# LE1-4.net
KiCad netlist of a schematic drawn in EAGLE
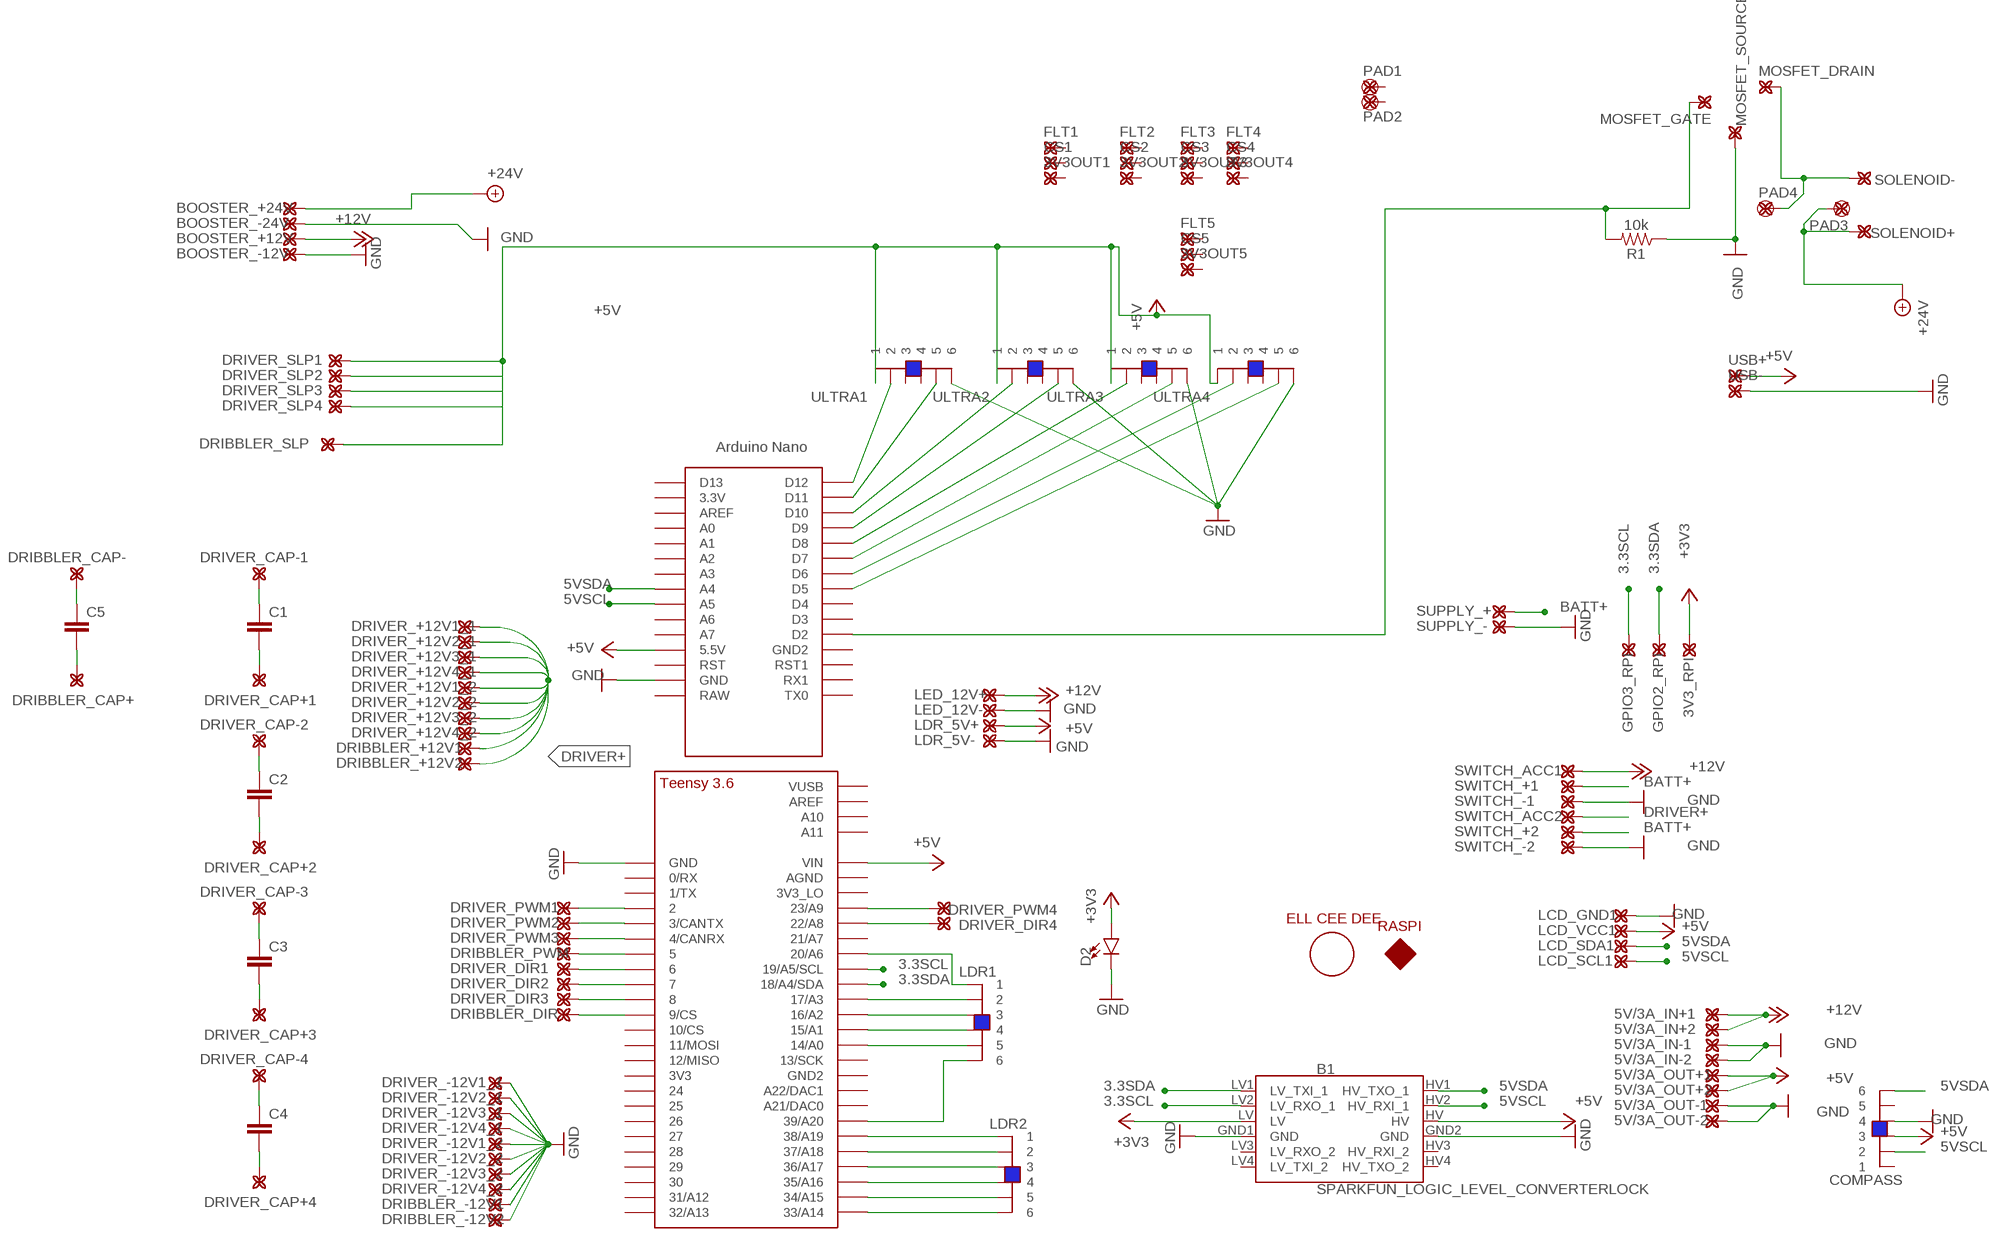
[diagram p0: schematic, sheet 1]

(export (version "E")
  (design (tool "Eeschema 10.0.6"))
  (components
    (comp (ref "3V3OUT1")
      (value "BETTERPAD_2.54")
      (footprint "eagle-import:SUPERIORSIM")
      (libsource (lib "eagle-import") (part "BETTERPAD_2.54"))
    )
    (comp (ref "3V3OUT2")
      (value "BETTERPAD_2.54")
      (footprint "eagle-import:SUPERIORSIM")
      (libsource (lib "eagle-import") (part "BETTERPAD_2.54"))
    )
    (comp (ref "3V3OUT3")
      (value "BETTERPAD_2.54")
      (footprint "eagle-import:SUPERIORSIM")
      (libsource (lib "eagle-import") (part "BETTERPAD_2.54"))
    )
    (comp (ref "3V3OUT4")
      (value "BETTERPAD_2.54")
      (footprint "eagle-import:SUPERIORSIM")
      (libsource (lib "eagle-import") (part "BETTERPAD_2.54"))
    )
    (comp (ref "3V3OUT5")
      (value "BETTERPAD_2.54")
      (footprint "eagle-import:SUPERIORSIM")
      (libsource (lib "eagle-import") (part "BETTERPAD_2.54"))
    )
    (comp (ref "3V3_RPI")
      (value "BETTERPAD_2.54")
      (footprint "eagle-import:SUPERIORSIM")
      (libsource (lib "eagle-import") (part "BETTERPAD_2.54"))
    )
    (comp (ref "5V/3A_IN+1")
      (value "BETTERPAD_2.54")
      (footprint "eagle-import:SUPERIORSIM")
      (libsource (lib "eagle-import") (part "BETTERPAD_2.54"))
    )
    (comp (ref "5V/3A_IN+2")
      (value "BETTERPAD_2.54")
      (footprint "eagle-import:SUPERIORSIM")
      (libsource (lib "eagle-import") (part "BETTERPAD_2.54"))
    )
    (comp (ref "5V/3A_IN-1")
      (value "BETTERPAD_2.54")
      (footprint "eagle-import:SUPERIORSIM")
      (libsource (lib "eagle-import") (part "BETTERPAD_2.54"))
    )
    (comp (ref "5V/3A_IN-2")
      (value "BETTERPAD_2.54")
      (footprint "eagle-import:SUPERIORSIM")
      (libsource (lib "eagle-import") (part "BETTERPAD_2.54"))
    )
    (comp (ref "5V/3A_OUT+1")
      (value "BETTERPAD_2.54")
      (footprint "eagle-import:SUPERIORSIM")
      (libsource (lib "eagle-import") (part "BETTERPAD_2.54"))
    )
    (comp (ref "5V/3A_OUT+2")
      (value "BETTERPAD_2.54")
      (footprint "eagle-import:SUPERIORSIM")
      (libsource (lib "eagle-import") (part "BETTERPAD_2.54"))
    )
    (comp (ref "5V/3A_OUT-1")
      (value "BETTERPAD_2.54")
      (footprint "eagle-import:SUPERIORSIM")
      (libsource (lib "eagle-import") (part "BETTERPAD_2.54"))
    )
    (comp (ref "5V/3A_OUT-2")
      (value "BETTERPAD_2.54")
      (footprint "eagle-import:SUPERIORSIM")
      (libsource (lib "eagle-import") (part "BETTERPAD_2.54"))
    )
    (comp (ref "B1")
      (value "SPARKFUN_LOGIC_LEVEL_CONVERTERLOCK")
      (footprint "eagle-import:SPARKFUN_LOGIC_LEVEL_CONVERTER_LOCK")
      (libsource (lib "eagle-import") (part "SPARKFUN_LOGIC_LEVEL_CONVERTERLOCK"))
    )
    (comp (ref "BOOSTER_+12V")
      (value "BETTERPAD_2.54")
      (footprint "eagle-import:SUPERIORSIM")
      (libsource (lib "eagle-import") (part "BETTERPAD_2.54"))
    )
    (comp (ref "BOOSTER_+24V")
      (value "BETTERPAD_2.54")
      (footprint "eagle-import:SUPERIORSIM")
      (libsource (lib "eagle-import") (part "BETTERPAD_2.54"))
    )
    (comp (ref "BOOSTER_-12V")
      (value "BETTERPAD_2.54")
      (footprint "eagle-import:SUPERIORSIM")
      (libsource (lib "eagle-import") (part "BETTERPAD_2.54"))
    )
    (comp (ref "BOOSTER_-24V")
      (value "BETTERPAD_2.54")
      (footprint "eagle-import:SUPERIORSIM")
      (libsource (lib "eagle-import") (part "BETTERPAD_2.54"))
    )
    (comp (ref "C1")
      (value "C5/7.2")
      (footprint "eagle-import:C5B7.2")
      (libsource (lib "eagle-import") (part "C5/7.2"))
    )
    (comp (ref "C2")
      (value "C5/7.2")
      (footprint "eagle-import:C5B7.2")
      (libsource (lib "eagle-import") (part "C5/7.2"))
    )
    (comp (ref "C3")
      (value "C5/7.2")
      (footprint "eagle-import:C5B7.2")
      (libsource (lib "eagle-import") (part "C5/7.2"))
    )
    (comp (ref "C4")
      (value "C5/7.2")
      (footprint "eagle-import:C5B7.2")
      (libsource (lib "eagle-import") (part "C5/7.2"))
    )
    (comp (ref "C5")
      (value "C5/7.2")
      (footprint "eagle-import:C5B7.2")
      (libsource (lib "eagle-import") (part "C5/7.2"))
    )
    (comp (ref "COMPASS")
      (value "6P6C_FEMALESMD")
      (footprint "eagle-import:6P6C_FEMALE")
      (libsource (lib "eagle-import") (part "6P6C_FEMALESMD"))
    )
    (comp (ref "CS1")
      (value "BETTERPAD_2.54")
      (footprint "eagle-import:SUPERIORSIM")
      (libsource (lib "eagle-import") (part "BETTERPAD_2.54"))
    )
    (comp (ref "CS2")
      (value "BETTERPAD_2.54")
      (footprint "eagle-import:SUPERIORSIM")
      (libsource (lib "eagle-import") (part "BETTERPAD_2.54"))
    )
    (comp (ref "CS3")
      (value "BETTERPAD_2.54")
      (footprint "eagle-import:SUPERIORSIM")
      (libsource (lib "eagle-import") (part "BETTERPAD_2.54"))
    )
    (comp (ref "CS4")
      (value "BETTERPAD_2.54")
      (footprint "eagle-import:SUPERIORSIM")
      (libsource (lib "eagle-import") (part "BETTERPAD_2.54"))
    )
    (comp (ref "CS5")
      (value "BETTERPAD_2.54")
      (footprint "eagle-import:SUPERIORSIM")
      (libsource (lib "eagle-import") (part "BETTERPAD_2.54"))
    )
    (comp (ref "D2")
      (value "LED-3MM-NO_SILK")
      (footprint "eagle-import:LED_3MM-NS")
      (libsource (lib "eagle-import") (part "LED-3MM-NO_SILK"))
    )
    (comp (ref "DRIBBLER_+12V1")
      (value "BETTERPAD_2.54")
      (footprint "eagle-import:SUPERIORSIM")
      (libsource (lib "eagle-import") (part "BETTERPAD_2.54"))
    )
    (comp (ref "DRIBBLER_+12V2")
      (value "BETTERPAD_2.54")
      (footprint "eagle-import:SUPERIORSIM")
      (libsource (lib "eagle-import") (part "BETTERPAD_2.54"))
    )
    (comp (ref "DRIBBLER_-12V1")
      (value "BETTERPAD_2.54")
      (footprint "eagle-import:SUPERIORSIM")
      (libsource (lib "eagle-import") (part "BETTERPAD_2.54"))
    )
    (comp (ref "DRIBBLER_-12V2")
      (value "BETTERPAD_2.54")
      (footprint "eagle-import:SUPERIORSIM")
      (libsource (lib "eagle-import") (part "BETTERPAD_2.54"))
    )
    (comp (ref "DRIBBLER_CAP+")
      (value "BETTERPAD_2.54")
      (footprint "eagle-import:SUPERIORSIM")
      (libsource (lib "eagle-import") (part "BETTERPAD_2.54"))
    )
    (comp (ref "DRIBBLER_CAP-")
      (value "BETTERPAD_2.54")
      (footprint "eagle-import:SUPERIORSIM")
      (libsource (lib "eagle-import") (part "BETTERPAD_2.54"))
    )
    (comp (ref "DRIBBLER_DIR")
      (value "BETTERPAD_2.54")
      (footprint "eagle-import:SUPERIORSIM")
      (libsource (lib "eagle-import") (part "BETTERPAD_2.54"))
    )
    (comp (ref "DRIBBLER_PWM")
      (value "BETTERPAD_2.54")
      (footprint "eagle-import:SUPERIORSIM")
      (libsource (lib "eagle-import") (part "BETTERPAD_2.54"))
    )
    (comp (ref "DRIBBLER_SLP")
      (value "BETTERPAD_2.54")
      (footprint "eagle-import:SUPERIORSIM")
      (libsource (lib "eagle-import") (part "BETTERPAD_2.54"))
    )
    (comp (ref "DRIVER_+12V1_1")
      (value "BETTERPAD_2.54")
      (footprint "eagle-import:SUPERIORSIM")
      (libsource (lib "eagle-import") (part "BETTERPAD_2.54"))
    )
    (comp (ref "DRIVER_+12V1_2")
      (value "BETTERPAD_2.54")
      (footprint "eagle-import:SUPERIORSIM")
      (libsource (lib "eagle-import") (part "BETTERPAD_2.54"))
    )
    (comp (ref "DRIVER_+12V2_1")
      (value "BETTERPAD_2.54")
      (footprint "eagle-import:SUPERIORSIM")
      (libsource (lib "eagle-import") (part "BETTERPAD_2.54"))
    )
    (comp (ref "DRIVER_+12V2_2")
      (value "BETTERPAD_2.54")
      (footprint "eagle-import:SUPERIORSIM")
      (libsource (lib "eagle-import") (part "BETTERPAD_2.54"))
    )
    (comp (ref "DRIVER_+12V3_1")
      (value "BETTERPAD_2.54")
      (footprint "eagle-import:SUPERIORSIM")
      (libsource (lib "eagle-import") (part "BETTERPAD_2.54"))
    )
    (comp (ref "DRIVER_+12V3_2")
      (value "BETTERPAD_2.54")
      (footprint "eagle-import:SUPERIORSIM")
      (libsource (lib "eagle-import") (part "BETTERPAD_2.54"))
    )
    (comp (ref "DRIVER_+12V4_1")
      (value "BETTERPAD_2.54")
      (footprint "eagle-import:SUPERIORSIM")
      (libsource (lib "eagle-import") (part "BETTERPAD_2.54"))
    )
    (comp (ref "DRIVER_+12V4_2")
      (value "BETTERPAD_2.54")
      (footprint "eagle-import:SUPERIORSIM")
      (libsource (lib "eagle-import") (part "BETTERPAD_2.54"))
    )
    (comp (ref "DRIVER_-12V1_1")
      (value "BETTERPAD_2.54")
      (footprint "eagle-import:SUPERIORSIM")
      (libsource (lib "eagle-import") (part "BETTERPAD_2.54"))
    )
    (comp (ref "DRIVER_-12V1_2")
      (value "BETTERPAD_2.54")
      (footprint "eagle-import:SUPERIORSIM")
      (libsource (lib "eagle-import") (part "BETTERPAD_2.54"))
    )
    (comp (ref "DRIVER_-12V2_1")
      (value "BETTERPAD_2.54")
      (footprint "eagle-import:SUPERIORSIM")
      (libsource (lib "eagle-import") (part "BETTERPAD_2.54"))
    )
    (comp (ref "DRIVER_-12V2_2")
      (value "BETTERPAD_2.54")
      (footprint "eagle-import:SUPERIORSIM")
      (libsource (lib "eagle-import") (part "BETTERPAD_2.54"))
    )
    (comp (ref "DRIVER_-12V3_1")
      (value "BETTERPAD_2.54")
      (footprint "eagle-import:SUPERIORSIM")
      (libsource (lib "eagle-import") (part "BETTERPAD_2.54"))
    )
    (comp (ref "DRIVER_-12V3_2")
      (value "BETTERPAD_2.54")
      (footprint "eagle-import:SUPERIORSIM")
      (libsource (lib "eagle-import") (part "BETTERPAD_2.54"))
    )
    (comp (ref "DRIVER_-12V4_1")
      (value "BETTERPAD_2.54")
      (footprint "eagle-import:SUPERIORSIM")
      (libsource (lib "eagle-import") (part "BETTERPAD_2.54"))
    )
    (comp (ref "DRIVER_-12V4_2")
      (value "BETTERPAD_2.54")
      (footprint "eagle-import:SUPERIORSIM")
      (libsource (lib "eagle-import") (part "BETTERPAD_2.54"))
    )
    (comp (ref "DRIVER_CAP+1")
      (value "BETTERPAD_2.54")
      (footprint "eagle-import:SUPERIORSIM")
      (libsource (lib "eagle-import") (part "BETTERPAD_2.54"))
    )
    (comp (ref "DRIVER_CAP+2")
      (value "BETTERPAD_2.54")
      (footprint "eagle-import:SUPERIORSIM")
      (libsource (lib "eagle-import") (part "BETTERPAD_2.54"))
    )
    (comp (ref "DRIVER_CAP+3")
      (value "BETTERPAD_2.54")
      (footprint "eagle-import:SUPERIORSIM")
      (libsource (lib "eagle-import") (part "BETTERPAD_2.54"))
    )
    (comp (ref "DRIVER_CAP+4")
      (value "BETTERPAD_2.54")
      (footprint "eagle-import:SUPERIORSIM")
      (libsource (lib "eagle-import") (part "BETTERPAD_2.54"))
    )
    (comp (ref "DRIVER_CAP-1")
      (value "BETTERPAD_2.54")
      (footprint "eagle-import:SUPERIORSIM")
      (libsource (lib "eagle-import") (part "BETTERPAD_2.54"))
    )
    (comp (ref "DRIVER_CAP-2")
      (value "BETTERPAD_2.54")
      (footprint "eagle-import:SUPERIORSIM")
      (libsource (lib "eagle-import") (part "BETTERPAD_2.54"))
    )
    (comp (ref "DRIVER_CAP-3")
      (value "BETTERPAD_2.54")
      (footprint "eagle-import:SUPERIORSIM")
      (libsource (lib "eagle-import") (part "BETTERPAD_2.54"))
    )
    (comp (ref "DRIVER_CAP-4")
      (value "BETTERPAD_2.54")
      (footprint "eagle-import:SUPERIORSIM")
      (libsource (lib "eagle-import") (part "BETTERPAD_2.54"))
    )
    (comp (ref "DRIVER_DIR1")
      (value "BETTERPAD_2.54")
      (footprint "eagle-import:SUPERIORSIM")
      (libsource (lib "eagle-import") (part "BETTERPAD_2.54"))
    )
    (comp (ref "DRIVER_DIR2")
      (value "BETTERPAD_2.54")
      (footprint "eagle-import:SUPERIORSIM")
      (libsource (lib "eagle-import") (part "BETTERPAD_2.54"))
    )
    (comp (ref "DRIVER_DIR3")
      (value "BETTERPAD_2.54")
      (footprint "eagle-import:SUPERIORSIM")
      (libsource (lib "eagle-import") (part "BETTERPAD_2.54"))
    )
    (comp (ref "DRIVER_DIR4")
      (value "BETTERPAD_2.54")
      (footprint "eagle-import:SUPERIORSIM")
      (libsource (lib "eagle-import") (part "BETTERPAD_2.54"))
    )
    (comp (ref "DRIVER_PWM1")
      (value "BETTERPAD_2.54")
      (footprint "eagle-import:SUPERIORSIM")
      (libsource (lib "eagle-import") (part "BETTERPAD_2.54"))
    )
    (comp (ref "DRIVER_PWM2")
      (value "BETTERPAD_2.54")
      (footprint "eagle-import:SUPERIORSIM")
      (libsource (lib "eagle-import") (part "BETTERPAD_2.54"))
    )
    (comp (ref "DRIVER_PWM3")
      (value "BETTERPAD_2.54")
      (footprint "eagle-import:SUPERIORSIM")
      (libsource (lib "eagle-import") (part "BETTERPAD_2.54"))
    )
    (comp (ref "DRIVER_PWM4")
      (value "BETTERPAD_2.54")
      (footprint "eagle-import:SUPERIORSIM")
      (libsource (lib "eagle-import") (part "BETTERPAD_2.54"))
    )
    (comp (ref "DRIVER_SLP1")
      (value "BETTERPAD_2.54")
      (footprint "eagle-import:SUPERIORSIM")
      (libsource (lib "eagle-import") (part "BETTERPAD_2.54"))
    )
    (comp (ref "DRIVER_SLP2")
      (value "BETTERPAD_2.54")
      (footprint "eagle-import:SUPERIORSIM")
      (libsource (lib "eagle-import") (part "BETTERPAD_2.54"))
    )
    (comp (ref "DRIVER_SLP3")
      (value "BETTERPAD_2.54")
      (footprint "eagle-import:SUPERIORSIM")
      (libsource (lib "eagle-import") (part "BETTERPAD_2.54"))
    )
    (comp (ref "DRIVER_SLP4")
      (value "BETTERPAD_2.54")
      (footprint "eagle-import:SUPERIORSIM")
      (libsource (lib "eagle-import") (part "BETTERPAD_2.54"))
    )
    (comp (ref "FLT1")
      (value "BETTERPAD_2.54")
      (footprint "eagle-import:SUPERIORSIM")
      (libsource (lib "eagle-import") (part "BETTERPAD_2.54"))
    )
    (comp (ref "FLT2")
      (value "BETTERPAD_2.54")
      (footprint "eagle-import:SUPERIORSIM")
      (libsource (lib "eagle-import") (part "BETTERPAD_2.54"))
    )
    (comp (ref "FLT3")
      (value "BETTERPAD_2.54")
      (footprint "eagle-import:SUPERIORSIM")
      (libsource (lib "eagle-import") (part "BETTERPAD_2.54"))
    )
    (comp (ref "FLT4")
      (value "BETTERPAD_2.54")
      (footprint "eagle-import:SUPERIORSIM")
      (libsource (lib "eagle-import") (part "BETTERPAD_2.54"))
    )
    (comp (ref "FLT5")
      (value "BETTERPAD_2.54")
      (footprint "eagle-import:SUPERIORSIM")
      (libsource (lib "eagle-import") (part "BETTERPAD_2.54"))
    )
    (comp (ref "GPIO2_RPI")
      (value "BETTERPAD_2.54")
      (footprint "eagle-import:SUPERIORSIM")
      (libsource (lib "eagle-import") (part "BETTERPAD_2.54"))
    )
    (comp (ref "GPIO3_RPI")
      (value "BETTERPAD_2.54")
      (footprint "eagle-import:SUPERIORSIM")
      (libsource (lib "eagle-import") (part "BETTERPAD_2.54"))
    )
    (comp (ref "LCD1")
      (value "LCD-16X2SILK")
      (footprint "eagle-import:LCD-16X2")
      (libsource (lib "eagle-import") (part "LCD-16X2SILK"))
    )
    (comp (ref "LCD_GND1")
      (value "BETTERPAD_2.54")
      (footprint "eagle-import:SUPERIORSIM")
      (libsource (lib "eagle-import") (part "BETTERPAD_2.54"))
    )
    (comp (ref "LCD_SCL1")
      (value "BETTERPAD_2.54")
      (footprint "eagle-import:SUPERIORSIM")
      (libsource (lib "eagle-import") (part "BETTERPAD_2.54"))
    )
    (comp (ref "LCD_SDA1")
      (value "BETTERPAD_2.54")
      (footprint "eagle-import:SUPERIORSIM")
      (libsource (lib "eagle-import") (part "BETTERPAD_2.54"))
    )
    (comp (ref "LCD_VCC1")
      (value "BETTERPAD_2.54")
      (footprint "eagle-import:SUPERIORSIM")
      (libsource (lib "eagle-import") (part "BETTERPAD_2.54"))
    )
    (comp (ref "LDR1")
      (value "6P6C_FEMALESMD")
      (footprint "eagle-import:6P6C_FEMALE")
      (libsource (lib "eagle-import") (part "6P6C_FEMALESMD"))
    )
    (comp (ref "LDR2")
      (value "6P6C_FEMALESMD")
      (footprint "eagle-import:6P6C_FEMALE")
      (libsource (lib "eagle-import") (part "6P6C_FEMALESMD"))
    )
    (comp (ref "LDR_5V+")
      (value "BETTERPAD_2.54")
      (footprint "eagle-import:SUPERIORSIM")
      (libsource (lib "eagle-import") (part "BETTERPAD_2.54"))
    )
    (comp (ref "LDR_5V-")
      (value "BETTERPAD_2.54")
      (footprint "eagle-import:SUPERIORSIM")
      (libsource (lib "eagle-import") (part "BETTERPAD_2.54"))
    )
    (comp (ref "LED_12V+")
      (value "BETTERPAD_2.54")
      (footprint "eagle-import:SUPERIORSIM")
      (libsource (lib "eagle-import") (part "BETTERPAD_2.54"))
    )
    (comp (ref "LED_12V-")
      (value "BETTERPAD_2.54")
      (footprint "eagle-import:SUPERIORSIM")
      (libsource (lib "eagle-import") (part "BETTERPAD_2.54"))
    )
    (comp (ref "MOSFET_DRAIN")
      (value "BETTERPAD_2.54")
      (footprint "eagle-import:SUPERIORSIM")
      (libsource (lib "eagle-import") (part "BETTERPAD_2.54"))
    )
    (comp (ref "MOSFET_GATE")
      (value "BETTERPAD_2.54")
      (footprint "eagle-import:SUPERIORSIM")
      (libsource (lib "eagle-import") (part "BETTERPAD_2.54"))
    )
    (comp (ref "MOSFET_SOURCE")
      (value "BETTERPAD_2.54")
      (footprint "eagle-import:SUPERIORSIM")
      (libsource (lib "eagle-import") (part "BETTERPAD_2.54"))
    )
    (comp (ref "PAD1")
      (value "BETTERPAD_2.54/1.5")
      (footprint "eagle-import:1,5")
      (libsource (lib "eagle-import") (part "BETTERPAD_2.54/1.5"))
    )
    (comp (ref "PAD2")
      (value "BETTERPAD_2.54/1.5")
      (footprint "eagle-import:1,5")
      (libsource (lib "eagle-import") (part "BETTERPAD_2.54/1.5"))
    )
    (comp (ref "PAD3")
      (value "BETTERPAD_2.54/1.5")
      (footprint "eagle-import:1,5")
      (libsource (lib "eagle-import") (part "BETTERPAD_2.54/1.5"))
    )
    (comp (ref "PAD4")
      (value "BETTERPAD_2.54/1.5")
      (footprint "eagle-import:1,5")
      (libsource (lib "eagle-import") (part "BETTERPAD_2.54/1.5"))
    )
    (comp (ref "PCB1")
      (value "RPI3")
      (footprint "eagle-import:RPI3")
      (libsource (lib "eagle-import") (part "RPI3"))
    )
    (comp (ref "R1")
      (value "10k")
      (footprint "eagle-import:AXIAL-0.3")
      (libsource (lib "eagle-import") (part "10KOHM-HORIZ-1/4W-1%"))
    )
    (comp (ref "SOLENOID+")
      (value "BETTERPAD_2.54")
      (footprint "eagle-import:SUPERIORSIM")
      (libsource (lib "eagle-import") (part "BETTERPAD_2.54"))
    )
    (comp (ref "SOLENOID-")
      (value "BETTERPAD_2.54")
      (footprint "eagle-import:SUPERIORSIM")
      (libsource (lib "eagle-import") (part "BETTERPAD_2.54"))
    )
    (comp (ref "SUPPLY_+")
      (value "BETTERPAD_2.54")
      (footprint "eagle-import:SUPERIORSIM")
      (libsource (lib "eagle-import") (part "BETTERPAD_2.54"))
    )
    (comp (ref "SUPPLY_-")
      (value "BETTERPAD_2.54")
      (footprint "eagle-import:SUPERIORSIM")
      (libsource (lib "eagle-import") (part "BETTERPAD_2.54"))
    )
    (comp (ref "SWITCH_+1")
      (value "BETTERPAD_2.54")
      (footprint "eagle-import:SUPERIORSIM")
      (libsource (lib "eagle-import") (part "BETTERPAD_2.54"))
    )
    (comp (ref "SWITCH_+2")
      (value "BETTERPAD_2.54")
      (footprint "eagle-import:SUPERIORSIM")
      (libsource (lib "eagle-import") (part "BETTERPAD_2.54"))
    )
    (comp (ref "SWITCH_-1")
      (value "BETTERPAD_2.54")
      (footprint "eagle-import:SUPERIORSIM")
      (libsource (lib "eagle-import") (part "BETTERPAD_2.54"))
    )
    (comp (ref "SWITCH_-2")
      (value "BETTERPAD_2.54")
      (footprint "eagle-import:SUPERIORSIM")
      (libsource (lib "eagle-import") (part "BETTERPAD_2.54"))
    )
    (comp (ref "SWITCH_ACC1")
      (value "BETTERPAD_2.54")
      (footprint "eagle-import:SUPERIORSIM")
      (libsource (lib "eagle-import") (part "BETTERPAD_2.54"))
    )
    (comp (ref "SWITCH_ACC2")
      (value "BETTERPAD_2.54")
      (footprint "eagle-import:SUPERIORSIM")
      (libsource (lib "eagle-import") (part "BETTERPAD_2.54"))
    )
    (comp (ref "U$1")
      (value "TEENSY_3.5/3.6_BASIC")
      (footprint "eagle-import:TEENSY_3.5_3.6_BASIC")
      (libsource (lib "eagle-import") (part "TEENSY_3.5/3.6_BASIC"))
    )
    (comp (ref "U$2")
      (value "NANO")
      (footprint "eagle-import:NANO")
      (libsource (lib "eagle-import") (part "NANO"))
    )
    (comp (ref "ULTRA1")
      (value "6P6C_FEMALESMD")
      (footprint "eagle-import:6P6C_FEMALE")
      (libsource (lib "eagle-import") (part "6P6C_FEMALESMD"))
    )
    (comp (ref "ULTRA2")
      (value "6P6C_FEMALESMD")
      (footprint "eagle-import:6P6C_FEMALE")
      (libsource (lib "eagle-import") (part "6P6C_FEMALESMD"))
    )
    (comp (ref "ULTRA3")
      (value "6P6C_FEMALESMD")
      (footprint "eagle-import:6P6C_FEMALE")
      (libsource (lib "eagle-import") (part "6P6C_FEMALESMD"))
    )
    (comp (ref "ULTRA4")
      (value "6P6C_FEMALESMD")
      (footprint "eagle-import:6P6C_FEMALE")
      (libsource (lib "eagle-import") (part "6P6C_FEMALESMD"))
    )
    (comp (ref "USB+")
      (value "BETTERPAD_2.54")
      (footprint "eagle-import:SUPERIORSIM")
      (libsource (lib "eagle-import") (part "BETTERPAD_2.54"))
    )
    (comp (ref "USB-")
      (value "BETTERPAD_2.54")
      (footprint "eagle-import:SUPERIORSIM")
      (libsource (lib "eagle-import") (part "BETTERPAD_2.54"))
    )
  )
  (nets
    (net (code "1") (name "+3V3") (class "Default")
      (node (ref "3V3_RPI") (pin ".") (pinfunction "P_.") (pintype "passive"))
      (node (ref "B1") (pin "LV") (pinfunction "LV_LV") (pintype "power_in"))
      (node (ref "D2") (pin "A") (pinfunction "A_A") (pintype "passive"))
    )
    (net (code "2") (name "+5V") (class "Default")
      (node (ref "5V/3A_OUT+1") (pin ".") (pinfunction "P_.") (pintype "passive"))
      (node (ref "5V/3A_OUT+2") (pin ".") (pinfunction "P_.") (pintype "passive"))
      (node (ref "B1") (pin "HV") (pinfunction "HV_HV") (pintype "power_in"))
      (node (ref "COMPASS") (pin "3") (pinfunction "3_3") (pintype "bidirectional"))
      (node (ref "DRIBBLER_SLP") (pin ".") (pinfunction "P_.") (pintype "passive"))
      (node (ref "DRIVER_SLP1") (pin ".") (pinfunction "P_.") (pintype "passive"))
      (node (ref "DRIVER_SLP2") (pin ".") (pinfunction "P_.") (pintype "passive"))
      (node (ref "DRIVER_SLP3") (pin ".") (pinfunction "P_.") (pintype "passive"))
      (node (ref "DRIVER_SLP4") (pin ".") (pinfunction "P_.") (pintype "passive"))
      (node (ref "LCD_VCC1") (pin ".") (pinfunction "P_.") (pintype "passive"))
      (node (ref "LDR_5V+") (pin ".") (pinfunction "P_.") (pintype "passive"))
      (node (ref "U$1") (pin "VIN") (pinfunction "VIN_VIN") (pintype "bidirectional"))
      (node (ref "U$2") (pin "5V") (pinfunction "5.5V_5V") (pintype "bidirectional"))
      (node (ref "ULTRA1") (pin "1") (pinfunction "1_1") (pintype "bidirectional"))
      (node (ref "ULTRA2") (pin "1") (pinfunction "1_1") (pintype "bidirectional"))
      (node (ref "ULTRA3") (pin "1") (pinfunction "1_1") (pintype "bidirectional"))
      (node (ref "ULTRA4") (pin "1") (pinfunction "1_1") (pintype "bidirectional"))
      (node (ref "USB+") (pin ".") (pinfunction "P_.") (pintype "passive"))
    )
    (net (code "3") (name "+12V") (class "Default")
      (node (ref "5V/3A_IN+1") (pin ".") (pinfunction "P_.") (pintype "passive"))
      (node (ref "5V/3A_IN+2") (pin ".") (pinfunction "P_.") (pintype "passive"))
      (node (ref "BOOSTER_+12V") (pin ".") (pinfunction "P_.") (pintype "passive"))
      (node (ref "LED_12V+") (pin ".") (pinfunction "P_.") (pintype "passive"))
      (node (ref "SWITCH_ACC1") (pin ".") (pinfunction "P_.") (pintype "passive"))
    )
    (net (code "4") (name "+24V") (class "Default")
      (node (ref "BOOSTER_+24V") (pin ".") (pinfunction "P_.") (pintype "passive"))
      (node (ref "PAD3") (pin "P$1") (pinfunction "P_P$1") (pintype "passive"))
      (node (ref "SOLENOID+") (pin ".") (pinfunction "P_.") (pintype "passive"))
    )
    (net (code "5") (name "/3.3SCL") (class "Default")
      (node (ref "B1") (pin "LV2") (pinfunction "LV_RXO_1_LV2") (pintype "bidirectional"))
      (node (ref "GPIO3_RPI") (pin ".") (pinfunction "P_.") (pintype "passive"))
      (node (ref "U$1") (pin "19/A5/SCL") (pinfunction "19/A5/SCL_19/A5/SCL") (pintype "bidirectional"))
    )
    (net (code "6") (name "/3.3SDA") (class "Default")
      (node (ref "B1") (pin "LV1") (pinfunction "LV_TXI_1_LV1") (pintype "bidirectional"))
      (node (ref "GPIO2_RPI") (pin ".") (pinfunction "P_.") (pintype "passive"))
      (node (ref "U$1") (pin "18/A4/SDA") (pinfunction "18/A4/SDA_18/A4/SDA") (pintype "bidirectional"))
    )
    (net (code "7") (name "/5VSCL") (class "Default")
      (node (ref "B1") (pin "HV2") (pinfunction "HV_RXI_1_HV2") (pintype "bidirectional"))
      (node (ref "COMPASS") (pin "2") (pinfunction "2_2") (pintype "bidirectional"))
      (node (ref "LCD_SCL1") (pin ".") (pinfunction "P_.") (pintype "passive"))
      (node (ref "U$2") (pin "A5") (pinfunction "A5_A5") (pintype "bidirectional"))
    )
    (net (code "8") (name "/5VSDA") (class "Default")
      (node (ref "B1") (pin "HV1") (pinfunction "HV_TXO_1_HV1") (pintype "bidirectional"))
      (node (ref "COMPASS") (pin "6") (pinfunction "6_6") (pintype "bidirectional"))
      (node (ref "LCD_SDA1") (pin ".") (pinfunction "P_.") (pintype "passive"))
      (node (ref "U$2") (pin "A4") (pinfunction "A4_A4") (pintype "bidirectional"))
    )
    (net (code "9") (name "/BATT+") (class "Default")
      (node (ref "SUPPLY_+") (pin ".") (pinfunction "P_.") (pintype "passive"))
      (node (ref "SWITCH_+1") (pin ".") (pinfunction "P_.") (pintype "passive"))
      (node (ref "SWITCH_+2") (pin ".") (pinfunction "P_.") (pintype "passive"))
    )
    (net (code "10") (name "DRIVER+") (class "Default")
      (node (ref "DRIBBLER_+12V1") (pin ".") (pinfunction "P_.") (pintype "passive"))
      (node (ref "DRIBBLER_+12V2") (pin ".") (pinfunction "P_.") (pintype "passive"))
      (node (ref "DRIVER_+12V1_1") (pin ".") (pinfunction "P_.") (pintype "passive"))
      (node (ref "DRIVER_+12V1_2") (pin ".") (pinfunction "P_.") (pintype "passive"))
      (node (ref "DRIVER_+12V2_1") (pin ".") (pinfunction "P_.") (pintype "passive"))
      (node (ref "DRIVER_+12V2_2") (pin ".") (pinfunction "P_.") (pintype "passive"))
      (node (ref "DRIVER_+12V3_1") (pin ".") (pinfunction "P_.") (pintype "passive"))
      (node (ref "DRIVER_+12V3_2") (pin ".") (pinfunction "P_.") (pintype "passive"))
      (node (ref "DRIVER_+12V4_1") (pin ".") (pinfunction "P_.") (pintype "passive"))
      (node (ref "DRIVER_+12V4_2") (pin ".") (pinfunction "P_.") (pintype "passive"))
      (node (ref "SWITCH_ACC2") (pin ".") (pinfunction "P_.") (pintype "passive"))
    )
    (net (code "11") (name "GND") (class "Default")
      (node (ref "5V/3A_IN-1") (pin ".") (pinfunction "P_.") (pintype "passive"))
      (node (ref "5V/3A_IN-2") (pin ".") (pinfunction "P_.") (pintype "passive"))
      (node (ref "5V/3A_OUT-1") (pin ".") (pinfunction "P_.") (pintype "passive"))
      (node (ref "5V/3A_OUT-2") (pin ".") (pinfunction "P_.") (pintype "passive"))
      (node (ref "B1") (pin "GND1") (pinfunction "GND_GND1") (pintype "power_in"))
      (node (ref "B1") (pin "GND2") (pinfunction "GND_GND2") (pintype "power_in"))
      (node (ref "BOOSTER_-12V") (pin ".") (pinfunction "P_.") (pintype "passive"))
      (node (ref "BOOSTER_-24V") (pin ".") (pinfunction "P_.") (pintype "passive"))
      (node (ref "COMPASS") (pin "4") (pinfunction "4_4") (pintype "bidirectional"))
      (node (ref "D2") (pin "K") (pinfunction "C_K") (pintype "passive"))
      (node (ref "DRIBBLER_-12V1") (pin ".") (pinfunction "P_.") (pintype "passive"))
      (node (ref "DRIBBLER_-12V2") (pin ".") (pinfunction "P_.") (pintype "passive"))
      (node (ref "DRIVER_-12V1_1") (pin ".") (pinfunction "P_.") (pintype "passive"))
      (node (ref "DRIVER_-12V1_2") (pin ".") (pinfunction "P_.") (pintype "passive"))
      (node (ref "DRIVER_-12V2_1") (pin ".") (pinfunction "P_.") (pintype "passive"))
      (node (ref "DRIVER_-12V2_2") (pin ".") (pinfunction "P_.") (pintype "passive"))
      (node (ref "DRIVER_-12V3_1") (pin ".") (pinfunction "P_.") (pintype "passive"))
      (node (ref "DRIVER_-12V3_2") (pin ".") (pinfunction "P_.") (pintype "passive"))
      (node (ref "DRIVER_-12V4_1") (pin ".") (pinfunction "P_.") (pintype "passive"))
      (node (ref "DRIVER_-12V4_2") (pin ".") (pinfunction "P_.") (pintype "passive"))
      (node (ref "LCD_GND1") (pin ".") (pinfunction "P_.") (pintype "passive"))
      (node (ref "LDR_5V-") (pin ".") (pinfunction "P_.") (pintype "passive"))
      (node (ref "LED_12V-") (pin ".") (pinfunction "P_.") (pintype "passive"))
      (node (ref "MOSFET_SOURCE") (pin ".") (pinfunction "P_.") (pintype "passive"))
      (node (ref "R1") (pin "P$1") (pinfunction "1_P$1") (pintype "passive"))
      (node (ref "SUPPLY_-") (pin ".") (pinfunction "P_.") (pintype "passive"))
      (node (ref "SWITCH_-1") (pin ".") (pinfunction "P_.") (pintype "passive"))
      (node (ref "SWITCH_-2") (pin ".") (pinfunction "P_.") (pintype "passive"))
      (node (ref "U$1") (pin "GND") (pinfunction "GND_GND") (pintype "bidirectional"))
      (node (ref "U$2") (pin "GND") (pinfunction "GND_GND") (pintype "bidirectional"))
      (node (ref "ULTRA1") (pin "6") (pinfunction "6_6") (pintype "bidirectional"))
      (node (ref "ULTRA2") (pin "6") (pinfunction "6_6") (pintype "bidirectional"))
      (node (ref "ULTRA3") (pin "6") (pinfunction "6_6") (pintype "bidirectional"))
      (node (ref "ULTRA4") (pin "6") (pinfunction "6_6") (pintype "bidirectional"))
      (node (ref "USB-") (pin ".") (pinfunction "P_.") (pintype "passive"))
    )
    (net (code "12") (name "Net-(DRIBBLER_CAP+-P)") (class "Default")
      (node (ref "C5") (pin "2") (pinfunction "2_2") (pintype "passive"))
      (node (ref "DRIBBLER_CAP+") (pin ".") (pinfunction "P_.") (pintype "passive"))
    )
    (net (code "13") (name "Net-(DRIBBLER_CAP--P)") (class "Default")
      (node (ref "C5") (pin "1") (pinfunction "1_1") (pintype "passive"))
      (node (ref "DRIBBLER_CAP-") (pin ".") (pinfunction "P_.") (pintype "passive"))
    )
    (net (code "14") (name "Net-(DRIBBLER_DIR-P)") (class "Default")
      (node (ref "DRIBBLER_DIR") (pin ".") (pinfunction "P_.") (pintype "passive"))
      (node (ref "U$1") (pin "9/CS") (pinfunction "9/CS_9/CS") (pintype "bidirectional"))
    )
    (net (code "15") (name "Net-(DRIBBLER_PWM-P)") (class "Default")
      (node (ref "DRIBBLER_PWM") (pin ".") (pinfunction "P_.") (pintype "passive"))
      (node (ref "U$1") (pin "5") (pinfunction "5_5") (pintype "bidirectional"))
    )
    (net (code "16") (name "Net-(DRIVER_CAP+1-P)") (class "Default")
      (node (ref "C1") (pin "2") (pinfunction "2_2") (pintype "passive"))
      (node (ref "DRIVER_CAP+1") (pin ".") (pinfunction "P_.") (pintype "passive"))
    )
    (net (code "17") (name "Net-(DRIVER_CAP+2-P)") (class "Default")
      (node (ref "C2") (pin "2") (pinfunction "2_2") (pintype "passive"))
      (node (ref "DRIVER_CAP+2") (pin ".") (pinfunction "P_.") (pintype "passive"))
    )
    (net (code "18") (name "Net-(DRIVER_CAP+3-P)") (class "Default")
      (node (ref "C3") (pin "2") (pinfunction "2_2") (pintype "passive"))
      (node (ref "DRIVER_CAP+3") (pin ".") (pinfunction "P_.") (pintype "passive"))
    )
    (net (code "19") (name "Net-(DRIVER_CAP+4-P)") (class "Default")
      (node (ref "C4") (pin "2") (pinfunction "2_2") (pintype "passive"))
      (node (ref "DRIVER_CAP+4") (pin ".") (pinfunction "P_.") (pintype "passive"))
    )
    (net (code "20") (name "Net-(DRIVER_CAP-1-P)") (class "Default")
      (node (ref "C1") (pin "1") (pinfunction "1_1") (pintype "passive"))
      (node (ref "DRIVER_CAP-1") (pin ".") (pinfunction "P_.") (pintype "passive"))
    )
    (net (code "21") (name "Net-(DRIVER_CAP-2-P)") (class "Default")
      (node (ref "C2") (pin "1") (pinfunction "1_1") (pintype "passive"))
      (node (ref "DRIVER_CAP-2") (pin ".") (pinfunction "P_.") (pintype "passive"))
    )
    (net (code "22") (name "Net-(DRIVER_CAP-3-P)") (class "Default")
      (node (ref "C3") (pin "1") (pinfunction "1_1") (pintype "passive"))
      (node (ref "DRIVER_CAP-3") (pin ".") (pinfunction "P_.") (pintype "passive"))
    )
    (net (code "23") (name "Net-(DRIVER_CAP-4-P)") (class "Default")
      (node (ref "C4") (pin "1") (pinfunction "1_1") (pintype "passive"))
      (node (ref "DRIVER_CAP-4") (pin ".") (pinfunction "P_.") (pintype "passive"))
    )
    (net (code "24") (name "Net-(DRIVER_DIR1-P)") (class "Default")
      (node (ref "DRIVER_DIR1") (pin ".") (pinfunction "P_.") (pintype "passive"))
      (node (ref "U$1") (pin "6") (pinfunction "6_6") (pintype "bidirectional"))
    )
    (net (code "25") (name "Net-(DRIVER_DIR2-P)") (class "Default")
      (node (ref "DRIVER_DIR2") (pin ".") (pinfunction "P_.") (pintype "passive"))
      (node (ref "U$1") (pin "7") (pinfunction "7_7") (pintype "bidirectional"))
    )
    (net (code "26") (name "Net-(DRIVER_DIR3-P)") (class "Default")
      (node (ref "DRIVER_DIR3") (pin ".") (pinfunction "P_.") (pintype "passive"))
      (node (ref "U$1") (pin "8") (pinfunction "8_8") (pintype "bidirectional"))
    )
    (net (code "27") (name "Net-(DRIVER_DIR4-P)") (class "Default")
      (node (ref "DRIVER_DIR4") (pin ".") (pinfunction "P_.") (pintype "passive"))
      (node (ref "U$1") (pin "22/A8") (pinfunction "22/A8_22/A8") (pintype "bidirectional"))
    )
    (net (code "28") (name "Net-(DRIVER_PWM1-P)") (class "Default")
      (node (ref "DRIVER_PWM1") (pin ".") (pinfunction "P_.") (pintype "passive"))
      (node (ref "U$1") (pin "2") (pinfunction "2_2") (pintype "bidirectional"))
    )
    (net (code "29") (name "Net-(DRIVER_PWM2-P)") (class "Default")
      (node (ref "DRIVER_PWM2") (pin ".") (pinfunction "P_.") (pintype "passive"))
      (node (ref "U$1") (pin "3/CANTX") (pinfunction "3/CANTX_3/CANTX") (pintype "bidirectional"))
    )
    (net (code "30") (name "Net-(DRIVER_PWM3-P)") (class "Default")
      (node (ref "DRIVER_PWM3") (pin ".") (pinfunction "P_.") (pintype "passive"))
      (node (ref "U$1") (pin "4/CANRX") (pinfunction "4/CANRX_4/CANRX") (pintype "bidirectional"))
    )
    (net (code "31") (name "Net-(DRIVER_PWM4-P)") (class "Default")
      (node (ref "DRIVER_PWM4") (pin ".") (pinfunction "P_.") (pintype "passive"))
      (node (ref "U$1") (pin "23/A9") (pinfunction "23/A9_23/A9") (pintype "bidirectional"))
    )
    (net (code "32") (name "Net-(LDR1-Pad1)") (class "Default")
      (node (ref "LDR1") (pin "1") (pinfunction "1_1") (pintype "bidirectional"))
      (node (ref "U$1") (pin "20/A6") (pinfunction "20/A6_20/A6") (pintype "bidirectional"))
    )
    (net (code "33") (name "Net-(LDR1-Pad2)") (class "Default")
      (node (ref "LDR1") (pin "2") (pinfunction "2_2") (pintype "bidirectional"))
      (node (ref "U$1") (pin "17/A3") (pinfunction "17/A3_17/A3") (pintype "bidirectional"))
    )
    (net (code "34") (name "Net-(LDR1-Pad3)") (class "Default")
      (node (ref "LDR1") (pin "3") (pinfunction "3_3") (pintype "bidirectional"))
      (node (ref "U$1") (pin "16/A2") (pinfunction "16/A2_16/A2") (pintype "bidirectional"))
    )
    (net (code "35") (name "Net-(LDR1-Pad4)") (class "Default")
      (node (ref "LDR1") (pin "4") (pinfunction "4_4") (pintype "bidirectional"))
      (node (ref "U$1") (pin "15/A1") (pinfunction "15/A1_15/A1") (pintype "bidirectional"))
    )
    (net (code "36") (name "Net-(LDR1-Pad5)") (class "Default")
      (node (ref "LDR1") (pin "5") (pinfunction "5_5") (pintype "bidirectional"))
      (node (ref "U$1") (pin "14/A0") (pinfunction "14/A0_14/A0") (pintype "bidirectional"))
    )
    (net (code "37") (name "Net-(LDR1-Pad6)") (class "Default")
      (node (ref "LDR1") (pin "6") (pinfunction "6_6") (pintype "bidirectional"))
      (node (ref "U$1") (pin "39/A20") (pinfunction "39/A20_39/A20") (pintype "bidirectional"))
    )
    (net (code "38") (name "Net-(LDR2-Pad1)") (class "Default")
      (node (ref "LDR2") (pin "1") (pinfunction "1_1") (pintype "bidirectional"))
      (node (ref "U$1") (pin "38/A19") (pinfunction "38/A19_38/A19") (pintype "bidirectional"))
    )
    (net (code "39") (name "Net-(LDR2-Pad2)") (class "Default")
      (node (ref "LDR2") (pin "2") (pinfunction "2_2") (pintype "bidirectional"))
      (node (ref "U$1") (pin "37/A18") (pinfunction "37/A18_37/A18") (pintype "bidirectional"))
    )
    (net (code "40") (name "Net-(LDR2-Pad3)") (class "Default")
      (node (ref "LDR2") (pin "3") (pinfunction "3_3") (pintype "bidirectional"))
      (node (ref "U$1") (pin "36/A17") (pinfunction "36/A17_36/A17") (pintype "bidirectional"))
    )
    (net (code "41") (name "Net-(LDR2-Pad4)") (class "Default")
      (node (ref "LDR2") (pin "4") (pinfunction "4_4") (pintype "bidirectional"))
      (node (ref "U$1") (pin "35/A16") (pinfunction "35/A16_35/A16") (pintype "bidirectional"))
    )
    (net (code "42") (name "Net-(LDR2-Pad5)") (class "Default")
      (node (ref "LDR2") (pin "5") (pinfunction "5_5") (pintype "bidirectional"))
      (node (ref "U$1") (pin "34/A15") (pinfunction "34/A15_34/A15") (pintype "bidirectional"))
    )
    (net (code "43") (name "Net-(LDR2-Pad6)") (class "Default")
      (node (ref "LDR2") (pin "6") (pinfunction "6_6") (pintype "bidirectional"))
      (node (ref "U$1") (pin "33/A14") (pinfunction "33/A14_33/A14") (pintype "bidirectional"))
    )
    (net (code "44") (name "Net-(MOSFET_DRAIN-P)") (class "Default")
      (node (ref "MOSFET_DRAIN") (pin ".") (pinfunction "P_.") (pintype "passive"))
      (node (ref "PAD4") (pin "P$1") (pinfunction "P_P$1") (pintype "passive"))
      (node (ref "SOLENOID-") (pin ".") (pinfunction "P_.") (pintype "passive"))
    )
    (net (code "45") (name "Net-(MOSFET_GATE-P)") (class "Default")
      (node (ref "MOSFET_GATE") (pin ".") (pinfunction "P_.") (pintype "passive"))
      (node (ref "R1") (pin "P$2") (pinfunction "2_P$2") (pintype "passive"))
      (node (ref "U$2") (pin "D2") (pinfunction "D2_D2") (pintype "bidirectional"))
    )
    (net (code "46") (name "Net-(U$2-PadD5)") (class "Default")
      (node (ref "U$2") (pin "D5") (pinfunction "D5_D5") (pintype "bidirectional"))
      (node (ref "ULTRA4") (pin "5") (pinfunction "5_5") (pintype "bidirectional"))
    )
    (net (code "47") (name "Net-(U$2-PadD6)") (class "Default")
      (node (ref "U$2") (pin "D6") (pinfunction "D6_D6") (pintype "bidirectional"))
      (node (ref "ULTRA4") (pin "2") (pinfunction "2_2") (pintype "bidirectional"))
    )
    (net (code "48") (name "Net-(U$2-PadD7)") (class "Default")
      (node (ref "U$2") (pin "D7") (pinfunction "D7_D7") (pintype "bidirectional"))
      (node (ref "ULTRA3") (pin "5") (pinfunction "5_5") (pintype "bidirectional"))
    )
    (net (code "49") (name "Net-(U$2-PadD8)") (class "Default")
      (node (ref "U$2") (pin "D8") (pinfunction "D8_D8") (pintype "bidirectional"))
      (node (ref "ULTRA3") (pin "2") (pinfunction "2_2") (pintype "bidirectional"))
    )
    (net (code "50") (name "Net-(U$2-PadD9)") (class "Default")
      (node (ref "U$2") (pin "D9") (pinfunction "D9_D9") (pintype "bidirectional"))
      (node (ref "ULTRA2") (pin "5") (pinfunction "5_5") (pintype "bidirectional"))
    )
    (net (code "51") (name "Net-(U$2-PadD10)") (class "Default")
      (node (ref "U$2") (pin "D10") (pinfunction "D10_D10") (pintype "bidirectional"))
      (node (ref "ULTRA2") (pin "2") (pinfunction "2_2") (pintype "bidirectional"))
    )
    (net (code "52") (name "Net-(U$2-PadD11)") (class "Default")
      (node (ref "U$2") (pin "D11") (pinfunction "D11_D11") (pintype "bidirectional"))
      (node (ref "ULTRA1") (pin "5") (pinfunction "5_5") (pintype "bidirectional"))
    )
    (net (code "53") (name "Net-(U$2-PadD12)") (class "Default")
      (node (ref "U$2") (pin "D12") (pinfunction "D12_D12") (pintype "bidirectional"))
      (node (ref "ULTRA1") (pin "2") (pinfunction "2_2") (pintype "bidirectional"))
    )
    (net (code "54") (name "unconnected-(3V3OUT1-P-Pad.)") (class "Default")
      (node (ref "3V3OUT1") (pin ".") (pinfunction "P_.") (pintype "passive"))
    )
    (net (code "55") (name "unconnected-(3V3OUT2-P-Pad.)") (class "Default")
      (node (ref "3V3OUT2") (pin ".") (pinfunction "P_.") (pintype "passive"))
    )
    (net (code "56") (name "unconnected-(3V3OUT3-P-Pad.)") (class "Default")
      (node (ref "3V3OUT3") (pin ".") (pinfunction "P_.") (pintype "passive"))
    )
    (net (code "57") (name "unconnected-(3V3OUT4-P-Pad.)") (class "Default")
      (node (ref "3V3OUT4") (pin ".") (pinfunction "P_.") (pintype "passive"))
    )
    (net (code "58") (name "unconnected-(3V3OUT5-P-Pad.)") (class "Default")
      (node (ref "3V3OUT5") (pin ".") (pinfunction "P_.") (pintype "passive"))
    )
    (net (code "59") (name "unconnected-(B1-HV_RXI_2-PadHV3)") (class "Default")
      (node (ref "B1") (pin "HV3") (pinfunction "HV_RXI_2_HV3") (pintype "bidirectional"))
    )
    (net (code "60") (name "unconnected-(B1-HV_TXO_2-PadHV4)") (class "Default")
      (node (ref "B1") (pin "HV4") (pinfunction "HV_TXO_2_HV4") (pintype "bidirectional"))
    )
    (net (code "61") (name "unconnected-(B1-LV_RXO_2-PadLV3)") (class "Default")
      (node (ref "B1") (pin "LV3") (pinfunction "LV_RXO_2_LV3") (pintype "bidirectional"))
    )
    (net (code "62") (name "unconnected-(B1-LV_TXI_2-PadLV4)") (class "Default")
      (node (ref "B1") (pin "LV4") (pinfunction "LV_TXI_2_LV4") (pintype "bidirectional"))
    )
    (net (code "63") (name "unconnected-(COMPASS-Pad1)") (class "Default")
      (node (ref "COMPASS") (pin "1") (pinfunction "1_1") (pintype "bidirectional"))
    )
    (net (code "64") (name "unconnected-(COMPASS-Pad5)") (class "Default")
      (node (ref "COMPASS") (pin "5") (pinfunction "5_5") (pintype "bidirectional"))
    )
    (net (code "65") (name "unconnected-(CS1-P-Pad.)") (class "Default")
      (node (ref "CS1") (pin ".") (pinfunction "P_.") (pintype "passive"))
    )
    (net (code "66") (name "unconnected-(CS2-P-Pad.)") (class "Default")
      (node (ref "CS2") (pin ".") (pinfunction "P_.") (pintype "passive"))
    )
    (net (code "67") (name "unconnected-(CS3-P-Pad.)") (class "Default")
      (node (ref "CS3") (pin ".") (pinfunction "P_.") (pintype "passive"))
    )
    (net (code "68") (name "unconnected-(CS4-P-Pad.)") (class "Default")
      (node (ref "CS4") (pin ".") (pinfunction "P_.") (pintype "passive"))
    )
    (net (code "69") (name "unconnected-(CS5-P-Pad.)") (class "Default")
      (node (ref "CS5") (pin ".") (pinfunction "P_.") (pintype "passive"))
    )
    (net (code "70") (name "unconnected-(FLT1-P-Pad.)") (class "Default")
      (node (ref "FLT1") (pin ".") (pinfunction "P_.") (pintype "passive"))
    )
    (net (code "71") (name "unconnected-(FLT2-P-Pad.)") (class "Default")
      (node (ref "FLT2") (pin ".") (pinfunction "P_.") (pintype "passive"))
    )
    (net (code "72") (name "unconnected-(FLT3-P-Pad.)") (class "Default")
      (node (ref "FLT3") (pin ".") (pinfunction "P_.") (pintype "passive"))
    )
    (net (code "73") (name "unconnected-(FLT4-P-Pad.)") (class "Default")
      (node (ref "FLT4") (pin ".") (pinfunction "P_.") (pintype "passive"))
    )
    (net (code "74") (name "unconnected-(FLT5-P-Pad.)") (class "Default")
      (node (ref "FLT5") (pin ".") (pinfunction "P_.") (pintype "passive"))
    )
    (net (code "75") (name "unconnected-(PAD1-P-PadP$1)") (class "Default")
      (node (ref "PAD1") (pin "P$1") (pinfunction "P_P$1") (pintype "passive"))
    )
    (net (code "76") (name "unconnected-(PAD2-P-PadP$1)") (class "Default")
      (node (ref "PAD2") (pin "P$1") (pinfunction "P_P$1") (pintype "passive"))
    )
    (net (code "77") (name "unconnected-(U$1-A21{slash}DAC0-Pad21{slash}DAC0)") (class "Default")
      (node (ref "U$1") (pin "21/DAC0") (pinfunction "A21/DAC0_21/DAC0") (pintype "bidirectional"))
    )
    (net (code "78") (name "unconnected-(U$1-Pad0{slash}RX)") (class "Default")
      (node (ref "U$1") (pin "0/RX") (pinfunction "0/RX_0/RX") (pintype "bidirectional"))
    )
    (net (code "79") (name "unconnected-(U$1-Pad1{slash}TX)") (class "Default")
      (node (ref "U$1") (pin "1/TX") (pinfunction "1/TX_1/TX") (pintype "bidirectional"))
    )
    (net (code "80") (name "unconnected-(U$1-Pad3V3)") (class "Default")
      (node (ref "U$1") (pin "3V3") (pinfunction "3V3_3V3") (pintype "bidirectional"))
    )
    (net (code "81") (name "unconnected-(U$1-Pad3V3_LO)") (class "Default")
      (node (ref "U$1") (pin "3V3_LO") (pinfunction "3V3_LO_3V3_LO") (pintype "bidirectional"))
    )
    (net (code "82") (name "unconnected-(U$1-Pad10{slash}CS)") (class "Default")
      (node (ref "U$1") (pin "10/CS") (pinfunction "10/CS_10/CS") (pintype "bidirectional"))
    )
    (net (code "83") (name "unconnected-(U$1-Pad11{slash}MOSI)") (class "Default")
      (node (ref "U$1") (pin "11/MOSI") (pinfunction "11/MOSI_11/MOSI") (pintype "bidirectional"))
    )
    (net (code "84") (name "unconnected-(U$1-Pad12{slash}MISO)") (class "Default")
      (node (ref "U$1") (pin "12/MISO") (pinfunction "12/MISO_12/MISO") (pintype "bidirectional"))
    )
    (net (code "85") (name "unconnected-(U$1-Pad13{slash}SCK)") (class "Default")
      (node (ref "U$1") (pin "13/SCK") (pinfunction "13/SCK_13/SCK") (pintype "bidirectional"))
    )
    (net (code "86") (name "unconnected-(U$1-Pad21{slash}A7)") (class "Default")
      (node (ref "U$1") (pin "21/A7") (pinfunction "21/A7_21/A7") (pintype "bidirectional"))
    )
    (net (code "87") (name "unconnected-(U$1-Pad24)") (class "Default")
      (node (ref "U$1") (pin "24") (pinfunction "24_24") (pintype "bidirectional"))
    )
    (net (code "88") (name "unconnected-(U$1-Pad25)") (class "Default")
      (node (ref "U$1") (pin "25") (pinfunction "25_25") (pintype "bidirectional"))
    )
    (net (code "89") (name "unconnected-(U$1-Pad26)") (class "Default")
      (node (ref "U$1") (pin "26") (pinfunction "26_26") (pintype "bidirectional"))
    )
    (net (code "90") (name "unconnected-(U$1-Pad27)") (class "Default")
      (node (ref "U$1") (pin "27") (pinfunction "27_27") (pintype "bidirectional"))
    )
    (net (code "91") (name "unconnected-(U$1-Pad28)") (class "Default")
      (node (ref "U$1") (pin "28") (pinfunction "28_28") (pintype "bidirectional"))
    )
    (net (code "92") (name "unconnected-(U$1-Pad29)") (class "Default")
      (node (ref "U$1") (pin "29") (pinfunction "29_29") (pintype "bidirectional"))
    )
    (net (code "93") (name "unconnected-(U$1-Pad30)") (class "Default")
      (node (ref "U$1") (pin "30") (pinfunction "30_30") (pintype "bidirectional"))
    )
    (net (code "94") (name "unconnected-(U$1-Pad31{slash}A12)") (class "Default")
      (node (ref "U$1") (pin "31/A12") (pinfunction "31/A12_31/A12") (pintype "bidirectional"))
    )
    (net (code "95") (name "unconnected-(U$1-Pad32{slash}A13)") (class "Default")
      (node (ref "U$1") (pin "32/A13") (pinfunction "32/A13_32/A13") (pintype "bidirectional"))
    )
    (net (code "96") (name "unconnected-(U$1-PadA10)") (class "Default")
      (node (ref "U$1") (pin "A10") (pinfunction "A10_A10") (pintype "bidirectional"))
    )
    (net (code "97") (name "unconnected-(U$1-PadA11)") (class "Default")
      (node (ref "U$1") (pin "A11") (pinfunction "A11_A11") (pintype "bidirectional"))
    )
    (net (code "98") (name "unconnected-(U$1-PadA22{slash}DAC1)") (class "Default")
      (node (ref "U$1") (pin "A22/DAC1") (pinfunction "A22/DAC1_A22/DAC1") (pintype "bidirectional"))
    )
    (net (code "99") (name "unconnected-(U$1-PadAGND)") (class "Default")
      (node (ref "U$1") (pin "AGND") (pinfunction "AGND_AGND") (pintype "bidirectional"))
    )
    (net (code "100") (name "unconnected-(U$1-PadAREF)") (class "Default")
      (node (ref "U$1") (pin "AREF") (pinfunction "AREF_AREF") (pintype "bidirectional"))
    )
    (net (code "101") (name "unconnected-(U$1-PadGND2)") (class "Default")
      (node (ref "U$1") (pin "GND2") (pinfunction "GND2_GND2") (pintype "bidirectional"))
    )
    (net (code "102") (name "unconnected-(U$1-PadVUSB)") (class "Default")
      (node (ref "U$1") (pin "VUSB") (pinfunction "VUSB_VUSB") (pintype "bidirectional"))
    )
    (net (code "103") (name "unconnected-(U$2-GND2-PadGND1)") (class "Default")
      (node (ref "U$2") (pin "GND1") (pinfunction "GND2_GND1") (pintype "bidirectional"))
    )
    (net (code "104") (name "unconnected-(U$2-Pad3.3V)") (class "Default")
      (node (ref "U$2") (pin "3.3V") (pinfunction "3.3V_3.3V") (pintype "bidirectional"))
    )
    (net (code "105") (name "unconnected-(U$2-PadA0)") (class "Default")
      (node (ref "U$2") (pin "A0") (pinfunction "A0_A0") (pintype "bidirectional"))
    )
    (net (code "106") (name "unconnected-(U$2-PadA1)") (class "Default")
      (node (ref "U$2") (pin "A1") (pinfunction "A1_A1") (pintype "bidirectional"))
    )
    (net (code "107") (name "unconnected-(U$2-PadA2)") (class "Default")
      (node (ref "U$2") (pin "A2") (pinfunction "A2_A2") (pintype "bidirectional"))
    )
    (net (code "108") (name "unconnected-(U$2-PadA3)") (class "Default")
      (node (ref "U$2") (pin "A3") (pinfunction "A3_A3") (pintype "bidirectional"))
    )
    (net (code "109") (name "unconnected-(U$2-PadA6)") (class "Default")
      (node (ref "U$2") (pin "A6") (pinfunction "A6_A6") (pintype "bidirectional"))
    )
    (net (code "110") (name "unconnected-(U$2-PadA7)") (class "Default")
      (node (ref "U$2") (pin "A7") (pinfunction "A7_A7") (pintype "bidirectional"))
    )
    (net (code "111") (name "unconnected-(U$2-PadAREF)") (class "Default")
      (node (ref "U$2") (pin "AREF") (pinfunction "AREF_AREF") (pintype "bidirectional"))
    )
    (net (code "112") (name "unconnected-(U$2-PadD3)") (class "Default")
      (node (ref "U$2") (pin "D3") (pinfunction "D3_D3") (pintype "bidirectional"))
    )
    (net (code "113") (name "unconnected-(U$2-PadD4)") (class "Default")
      (node (ref "U$2") (pin "D4") (pinfunction "D4_D4") (pintype "bidirectional"))
    )
    (net (code "114") (name "unconnected-(U$2-PadD13)") (class "Default")
      (node (ref "U$2") (pin "D13") (pinfunction "D13_D13") (pintype "bidirectional"))
    )
    (net (code "115") (name "unconnected-(U$2-PadRAW)") (class "Default")
      (node (ref "U$2") (pin "RAW") (pinfunction "RAW_RAW") (pintype "bidirectional"))
    )
    (net (code "116") (name "unconnected-(U$2-PadRST)") (class "Default")
      (node (ref "U$2") (pin "RST") (pinfunction "RST_RST") (pintype "bidirectional"))
    )
    (net (code "117") (name "unconnected-(U$2-PadRST1)") (class "Default")
      (node (ref "U$2") (pin "RST1") (pinfunction "RST1_RST1") (pintype "bidirectional"))
    )
    (net (code "118") (name "unconnected-(U$2-PadRX1)") (class "Default")
      (node (ref "U$2") (pin "RX1") (pinfunction "RX1_RX1") (pintype "bidirectional"))
    )
    (net (code "119") (name "unconnected-(U$2-PadTX0)") (class "Default")
      (node (ref "U$2") (pin "TX0") (pinfunction "TX0_TX0") (pintype "bidirectional"))
    )
    (net (code "120") (name "unconnected-(ULTRA1-Pad3)") (class "Default")
      (node (ref "ULTRA1") (pin "3") (pinfunction "3_3") (pintype "bidirectional"))
    )
    (net (code "121") (name "unconnected-(ULTRA1-Pad4)") (class "Default")
      (node (ref "ULTRA1") (pin "4") (pinfunction "4_4") (pintype "bidirectional"))
    )
    (net (code "122") (name "unconnected-(ULTRA2-Pad3)") (class "Default")
      (node (ref "ULTRA2") (pin "3") (pinfunction "3_3") (pintype "bidirectional"))
    )
    (net (code "123") (name "unconnected-(ULTRA2-Pad4)") (class "Default")
      (node (ref "ULTRA2") (pin "4") (pinfunction "4_4") (pintype "bidirectional"))
    )
    (net (code "124") (name "unconnected-(ULTRA3-Pad3)") (class "Default")
      (node (ref "ULTRA3") (pin "3") (pinfunction "3_3") (pintype "bidirectional"))
    )
    (net (code "125") (name "unconnected-(ULTRA3-Pad4)") (class "Default")
      (node (ref "ULTRA3") (pin "4") (pinfunction "4_4") (pintype "bidirectional"))
    )
    (net (code "126") (name "unconnected-(ULTRA4-Pad3)") (class "Default")
      (node (ref "ULTRA4") (pin "3") (pinfunction "3_3") (pintype "bidirectional"))
    )
    (net (code "127") (name "unconnected-(ULTRA4-Pad4)") (class "Default")
      (node (ref "ULTRA4") (pin "4") (pinfunction "4_4") (pintype "bidirectional"))
    )
  )
)
